# LowLevelv3.net
KiCad netlist of a schematic drawn in EAGLE
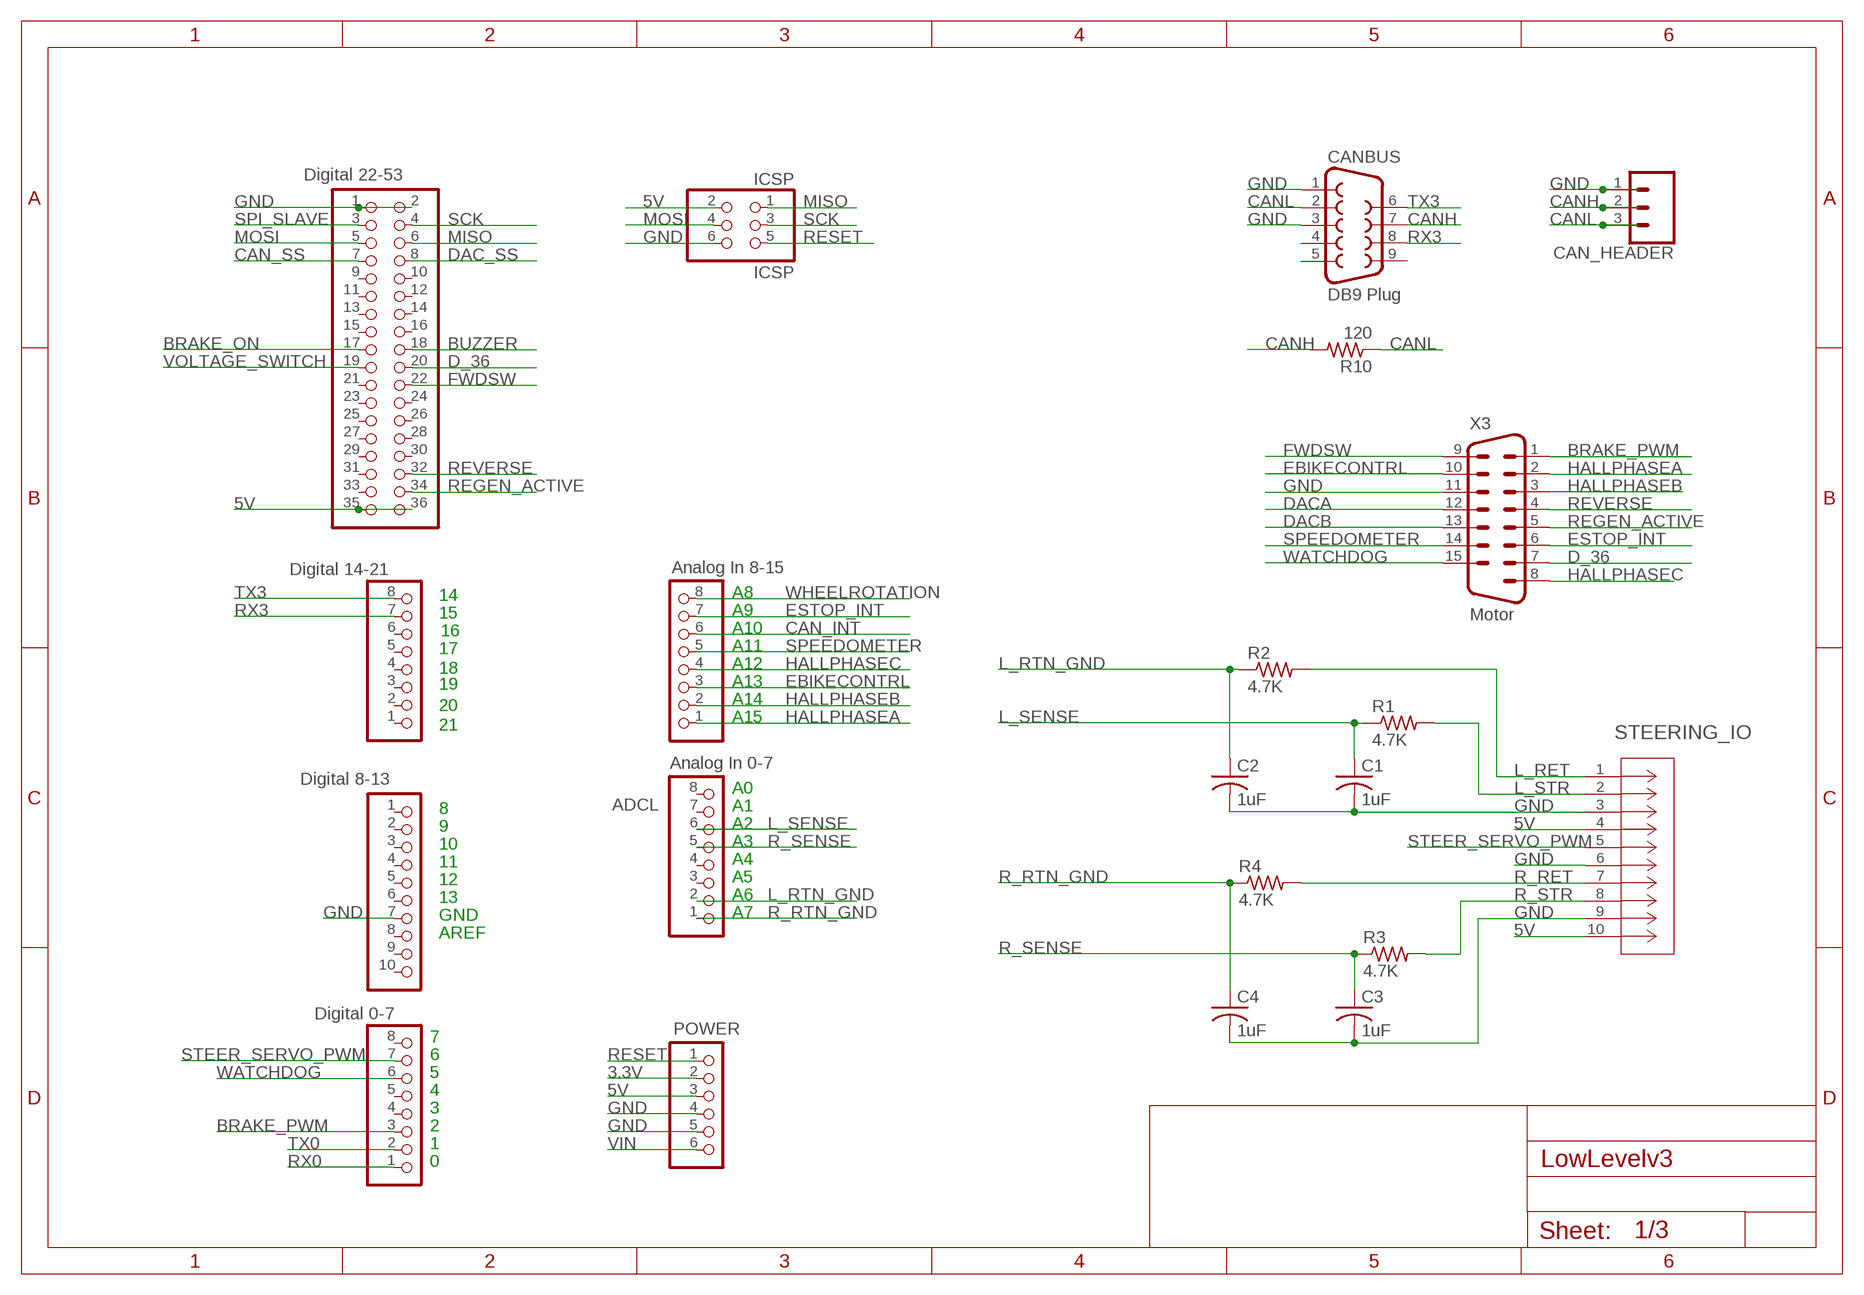
[diagram p0: schematic, sheet 1]
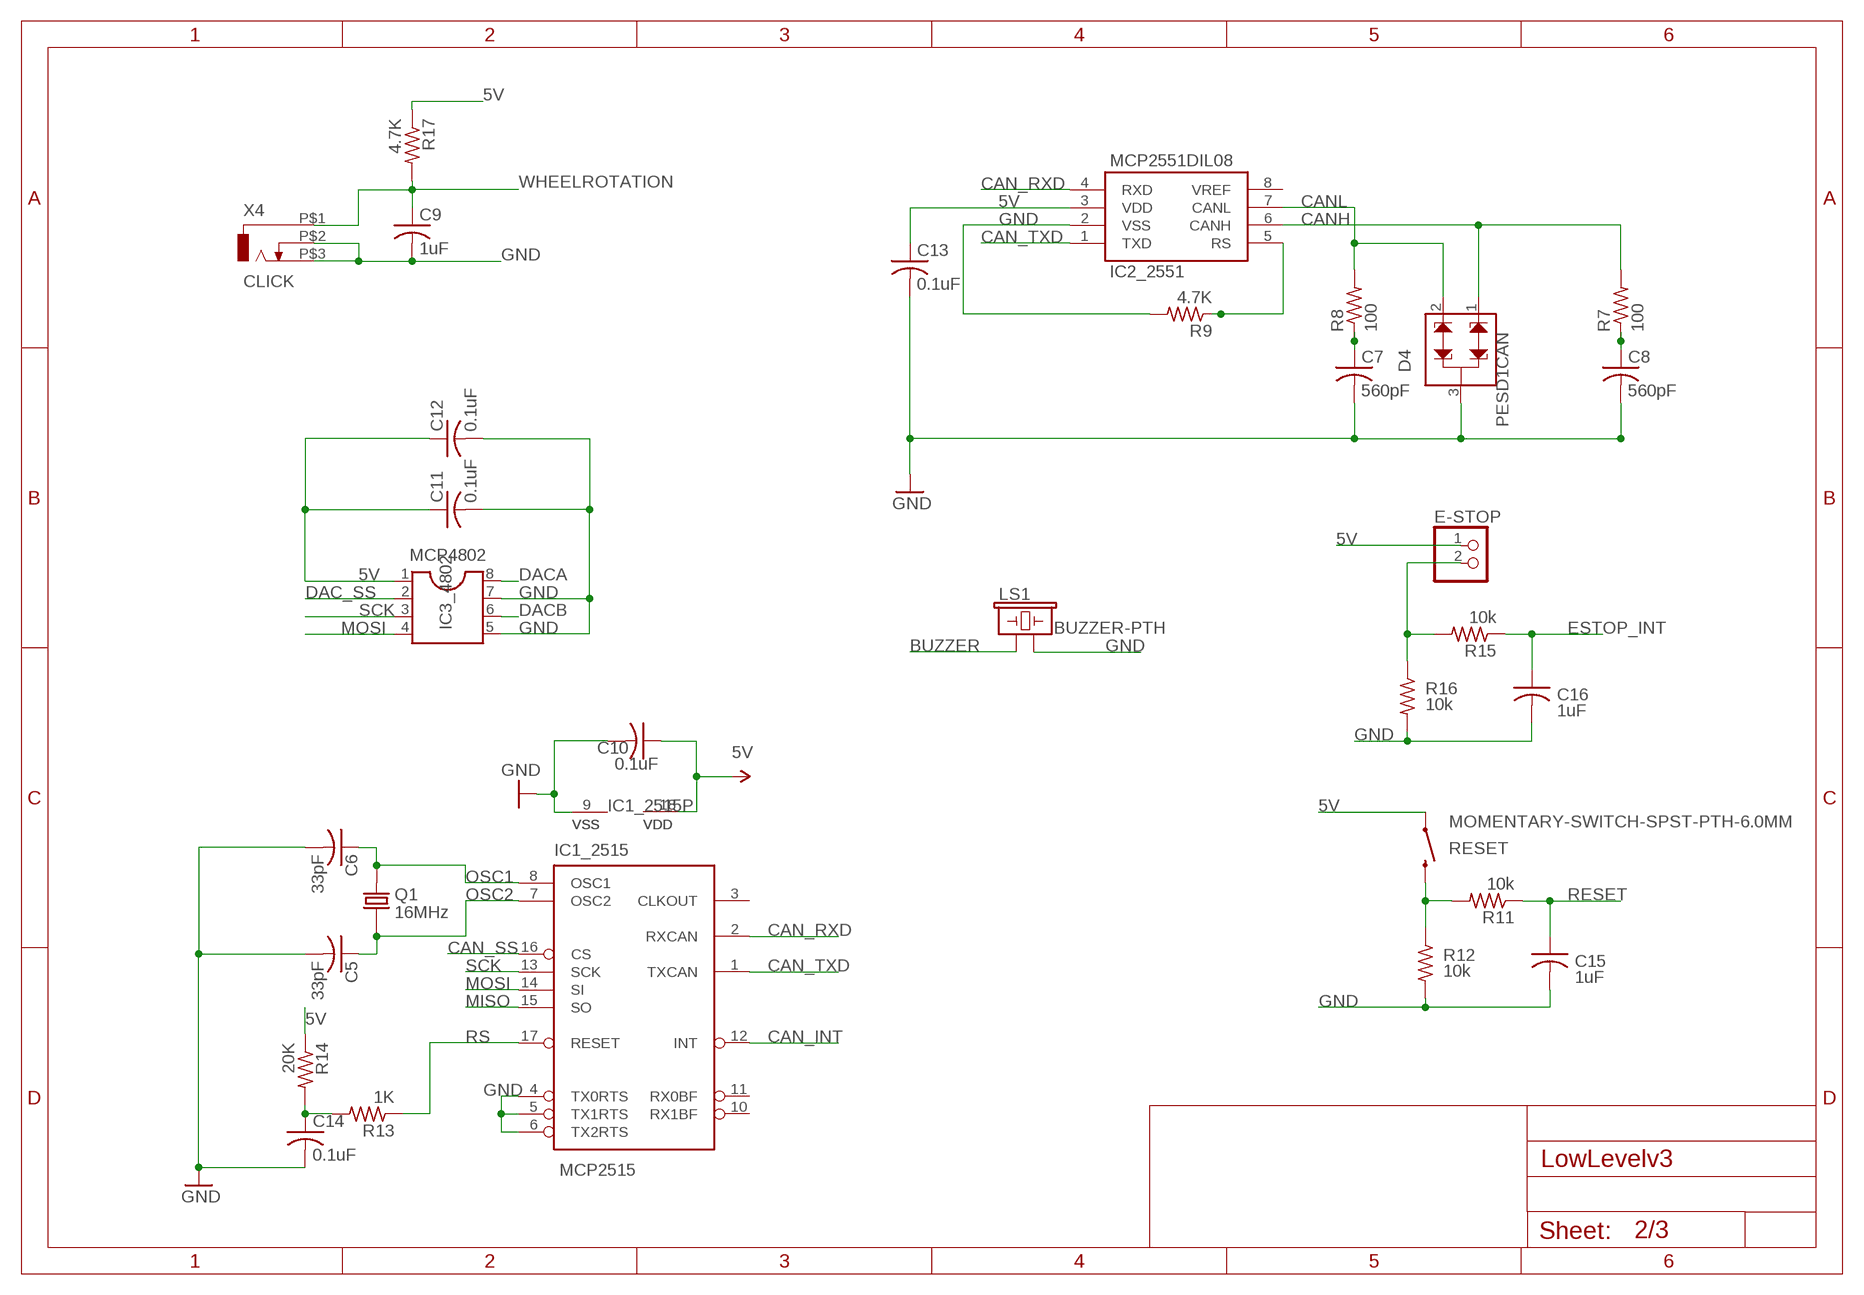
[diagram p1: schematic, sheet 2]
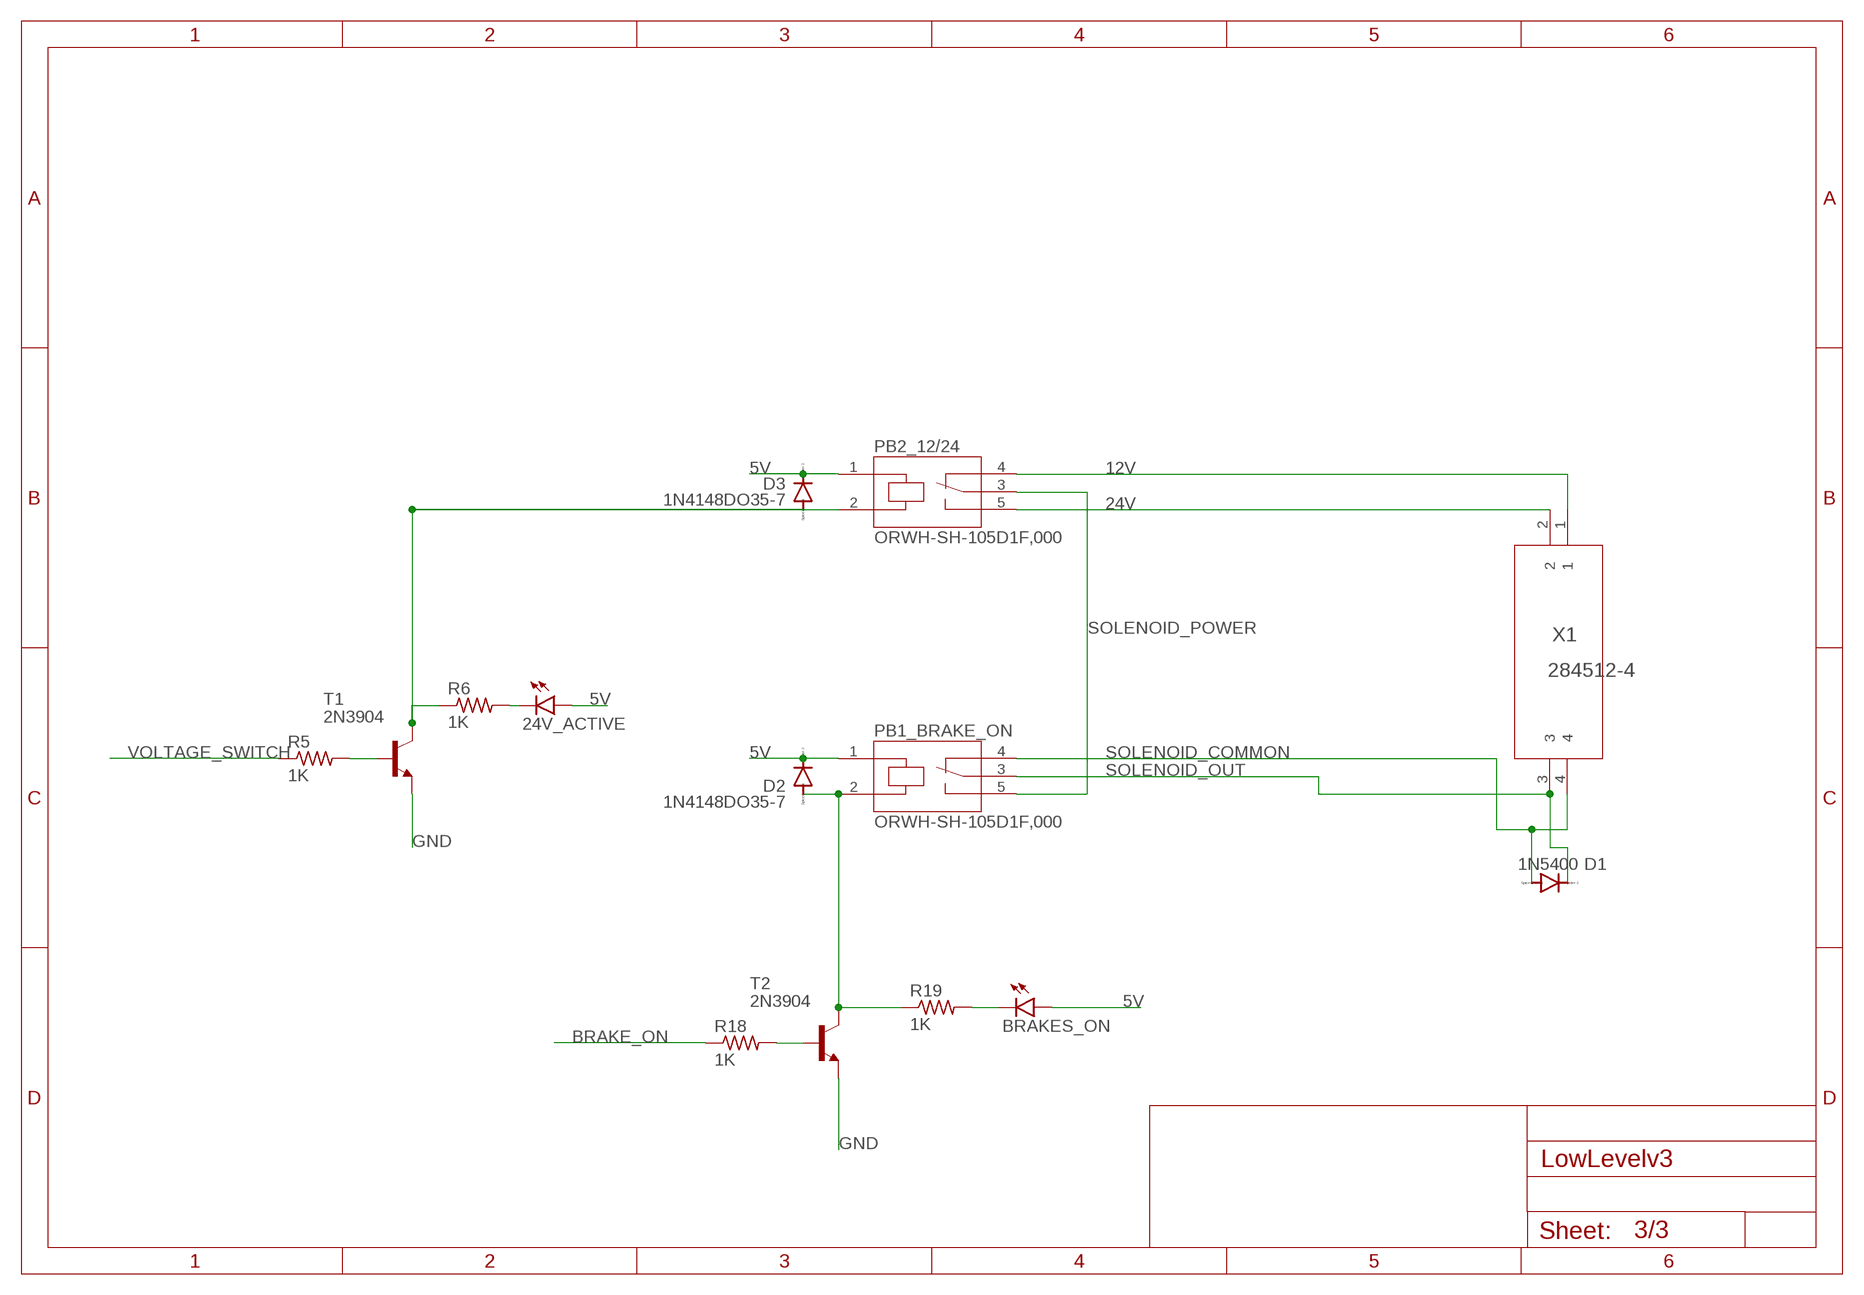
[diagram p2: schematic, sheet 3]

(export (version "E")
  (design (tool "Eeschema 10.0.6"))
  (components
    (comp (ref "ADCH")
      (value "Analog In 8-15")
      (footprint "eagle-import:1X08")
      (libsource (lib "eagle-import") (part "PINHD-1X8"))
    )
    (comp (ref "ADCL")
      (value "Analog In 0-7")
      (footprint "eagle-import:1X08")
      (libsource (lib "eagle-import") (part "PINHD-1X8"))
    )
    (comp (ref "C1")
      (value "1uF")
      (footprint "eagle-import:C1206")
      (libsource (lib "eagle-import") (part "C-USC1206"))
    )
    (comp (ref "C2")
      (value "1uF")
      (footprint "eagle-import:C1206")
      (libsource (lib "eagle-import") (part "C-USC1206"))
    )
    (comp (ref "C3")
      (value "1uF")
      (footprint "eagle-import:C1206")
      (libsource (lib "eagle-import") (part "C-USC1206"))
    )
    (comp (ref "C4")
      (value "1uF")
      (footprint "eagle-import:C1206")
      (libsource (lib "eagle-import") (part "C-USC1206"))
    )
    (comp (ref "CANBUS")
      (value "DB9 Plug")
      (footprint "eagle-import:DB9")
      (fields (field (name "SPICEPREFIX") "X"))
      (libsource (lib "eagle-import") (part "DB9FEMALE"))
    )
    (comp (ref "CAN_HEADER")
      (value "CONN_03-SCREW-5MM")
      (footprint "eagle-import:SCREWTERMINAL-5MM-3")
      (libsource (lib "eagle-import") (part "CONN_03-SCREW-5MM"))
    )
    (comp (ref "DIGITAL_0-7")
      (value "Digital 0-7")
      (footprint "eagle-import:1X08")
      (libsource (lib "eagle-import") (part "PINHD-1X8"))
    )
    (comp (ref "DIGITAL_8-13")
      (value "Digital 8-13")
      (footprint "eagle-import:1X10")
      (libsource (lib "eagle-import") (part "PINHD-1X10"))
    )
    (comp (ref "DIGITAL_14-21")
      (value "Digital 14-21")
      (footprint "eagle-import:1X08")
      (libsource (lib "eagle-import") (part "PINHD-1X8"))
    )
    (comp (ref "ICSP")
      (value "ICSP")
      (footprint "eagle-import:2X03")
      (libsource (lib "eagle-import") (part "PINHD-2X3"))
    )
    (comp (ref "MEGA_EXPANSION")
      (value "Digital 22-53")
      (footprint "eagle-import:PINHEAD_2X18")
      (libsource (lib "eagle-import") (part "PINHEAD_PINHD-2X18"))
    )
    (comp (ref "POWER")
      (value "PINHD-1X6")
      (footprint "eagle-import:1X06")
      (libsource (lib "eagle-import") (part "PINHD-1X6"))
    )
    (comp (ref "R1")
      (value "4.7K")
      (footprint "eagle-import:R1206")
      (libsource (lib "eagle-import") (part "R-US_R1206"))
    )
    (comp (ref "R2")
      (value "4.7K")
      (footprint "eagle-import:R1206")
      (libsource (lib "eagle-import") (part "R-US_R1206"))
    )
    (comp (ref "R3")
      (value "4.7K")
      (footprint "eagle-import:R1206")
      (libsource (lib "eagle-import") (part "R-US_R1206"))
    )
    (comp (ref "R4")
      (value "4.7K")
      (footprint "eagle-import:R1206")
      (libsource (lib "eagle-import") (part "R-US_R1206"))
    )
    (comp (ref "R10")
      (value "120")
      (footprint "eagle-import:R1206")
      (libsource (lib "eagle-import") (part "R-US_R1206"))
    )
    (comp (ref "STEERING_IO")
      (value "5-104069-4")
      (footprint "eagle-import:CONN_5-104069-4_TYCO")
      (fields (field (name "MANUFACTURER_PART_NUMBER") "51040694"))
      (libsource (lib "eagle-import") (part "5-104069-4"))
    )
    (comp (ref "X3")
      (value "Motor")
      (footprint "eagle-import:182-015-MALE")
      (libsource (lib "eagle-import") (part "M15-182"))
    )
    (comp (ref "24V_ACTIVE")
      (value "LED3MM")
      (footprint "eagle-import:LED3MM")
      (libsource (lib "eagle-import") (part "LED3MM"))
    )
    (comp (ref "BRAKES_ON")
      (value "LED3MM")
      (footprint "eagle-import:LED3MM")
      (libsource (lib "eagle-import") (part "LED3MM"))
    )
    (comp (ref "D1")
      (value "1N5400")
      (footprint "eagle-import:DO201-15")
      (libsource (lib "eagle-import") (part "1N5400"))
    )
    (comp (ref "D2")
      (value "1N4148DO35-7")
      (footprint "eagle-import:DO35-7")
      (libsource (lib "eagle-import") (part "1N4148DO35-7"))
    )
    (comp (ref "D3")
      (value "1N4148DO35-7")
      (footprint "eagle-import:DO35-7")
      (libsource (lib "eagle-import") (part "1N4148DO35-7"))
    )
    (comp (ref "PB1_BRAKE_ON")
      (value "ORWH-SH-105D1F,000")
      (footprint "eagle-import:TE_ORWH-SH-105D1F,000")
      (fields (field (name "DIGI-KEY_PART_NUMBER") "PB2032-ND") (field (name "MF") "TE"))
      (libsource (lib "eagle-import") (part "ORWH-SH-105D1F,000"))
    )
    (comp (ref "PB2_12/24")
      (value "ORWH-SH-105D1F,000")
      (footprint "eagle-import:TE_ORWH-SH-105D1F,000")
      (fields (field (name "DIGI-KEY_PART_NUMBER") "PB2032-ND") (field (name "MF") "TE"))
      (libsource (lib "eagle-import") (part "ORWH-SH-105D1F,000"))
    )
    (comp (ref "R5")
      (value "1K")
      (footprint "eagle-import:R1206")
      (libsource (lib "eagle-import") (part "R-US_R1206"))
    )
    (comp (ref "R6")
      (value "1K")
      (footprint "eagle-import:R1206")
      (libsource (lib "eagle-import") (part "R-US_R1206"))
    )
    (comp (ref "R18")
      (value "1K")
      (footprint "eagle-import:R1206")
      (libsource (lib "eagle-import") (part "R-US_R1206"))
    )
    (comp (ref "R19")
      (value "1K")
      (footprint "eagle-import:R1206")
      (libsource (lib "eagle-import") (part "R-US_R1206"))
    )
    (comp (ref "T1")
      (value "2N3904")
      (footprint "eagle-import:TO92")
      (libsource (lib "eagle-import") (part "2N3904"))
    )
    (comp (ref "T2")
      (value "2N3904")
      (footprint "eagle-import:TO92")
      (libsource (lib "eagle-import") (part "2N3904"))
    )
    (comp (ref "X1")
      (value "284512-4")
      (footprint "eagle-import:284512-4")
      (fields (field (name "MANUFACTURER_PART_NUMBER") "2845124"))
      (libsource (lib "eagle-import") (part "284512-4"))
    )
    (comp (ref "C5")
      (value "33pF")
      (footprint "eagle-import:C1206")
      (libsource (lib "eagle-import") (part "C-USC1206"))
    )
    (comp (ref "C6")
      (value "33pF")
      (footprint "eagle-import:C1206")
      (libsource (lib "eagle-import") (part "C-USC1206"))
    )
    (comp (ref "C7")
      (value "560pF")
      (footprint "eagle-import:C1206")
      (libsource (lib "eagle-import") (part "C-USC1206"))
    )
    (comp (ref "C8")
      (value "560pF")
      (footprint "eagle-import:C1206")
      (libsource (lib "eagle-import") (part "C-USC1206"))
    )
    (comp (ref "C9")
      (value "1uF")
      (footprint "eagle-import:C1206")
      (libsource (lib "eagle-import") (part "C-USC1206"))
    )
    (comp (ref "C10")
      (value "0.1uF")
      (footprint "eagle-import:C1206")
      (libsource (lib "eagle-import") (part "C-USC1206"))
    )
    (comp (ref "C11")
      (value "0.1uF")
      (footprint "eagle-import:C1206")
      (libsource (lib "eagle-import") (part "C-USC1206"))
    )
    (comp (ref "C12")
      (value "0.1uF")
      (footprint "eagle-import:C1206")
      (libsource (lib "eagle-import") (part "C-USC1206"))
    )
    (comp (ref "C13")
      (value "0.1uF")
      (footprint "eagle-import:C1206")
      (libsource (lib "eagle-import") (part "C-USC1206"))
    )
    (comp (ref "C14")
      (value "0.1uF")
      (footprint "eagle-import:C1206")
      (libsource (lib "eagle-import") (part "C-USC1206"))
    )
    (comp (ref "C15")
      (value "1uF")
      (footprint "eagle-import:C1206")
      (libsource (lib "eagle-import") (part "C-USC1206"))
    )
    (comp (ref "C16")
      (value "1uF")
      (footprint "eagle-import:C1206")
      (libsource (lib "eagle-import") (part "C-USC1206"))
    )
    (comp (ref "D4")
      (value "PESD1CAN")
      (footprint "eagle-import:SPARKFUN-DISCRETESEMI_SOT23-3")
      (fields (field (name "SPICEPREFIX") "J"))
      (libsource (lib "eagle-import") (part "PESD1CAN"))
    )
    (comp (ref "E-STOP")
      (value "PINHD-1X2")
      (footprint "eagle-import:1X02")
      (libsource (lib "eagle-import") (part "PINHD-1X2"))
    )
    (comp (ref "IC1_2515")
      (value "MCP2515")
      (footprint "eagle-import:DIP18")
      (fields (field (name "SPICEPREFIX") "X"))
      (libsource (lib "eagle-import") (part "MCP2515(MCP2510)P"))
    )
    (comp (ref "IC2_2551")
      (value "MCP2551DIL08")
      (footprint "eagle-import:IC-PACKAGE_DIL08")
      (fields (field (name "SPICEPREFIX") "X"))
      (libsource (lib "eagle-import") (part "MCP2551DIL08"))
    )
    (comp (ref "IC3_4802")
      (value "MCP4802")
      (footprint "eagle-import:DIL08")
      (libsource (lib "eagle-import") (part "DIL8"))
    )
    (comp (ref "LS1")
      (value "BUZZER-PTH")
      (footprint "eagle-import:BUZZER-12MM")
      (libsource (lib "eagle-import") (part "BUZZER-PTH"))
    )
    (comp (ref "Q1")
      (value "16MHz")
      (footprint "eagle-import:XTAL_ECS-160-20-46X")
      (fields
        (field (name "DIGI-KEY_PART_NUMBER") "XC1759-ND")
        (field (name "MF") "ECS Inc.")
        (field (name "MP") "ECS-160-20-46X")
        (field (name "SPICEPREFIX") "B")
      )
      (libsource (lib "eagle-import") (part "ECS-160-20-46X"))
    )
    (comp (ref "R7")
      (value "100")
      (footprint "eagle-import:R1206")
      (libsource (lib "eagle-import") (part "R-US_R1206"))
    )
    (comp (ref "R8")
      (value "100")
      (footprint "eagle-import:R1206")
      (libsource (lib "eagle-import") (part "R-US_R1206"))
    )
    (comp (ref "R9")
      (value "4.7K")
      (footprint "eagle-import:R1206")
      (libsource (lib "eagle-import") (part "R-US_R1206"))
    )
    (comp (ref "R11")
      (value "10k")
      (footprint "eagle-import:R1206")
      (libsource (lib "eagle-import") (part "R-US_R1206"))
    )
    (comp (ref "R12")
      (value "10k")
      (footprint "eagle-import:R1206")
      (libsource (lib "eagle-import") (part "R-US_R1206"))
    )
    (comp (ref "R13")
      (value "1K")
      (footprint "eagle-import:R1206")
      (libsource (lib "eagle-import") (part "R-US_R1206"))
    )
    (comp (ref "R14")
      (value "20K")
      (footprint "eagle-import:R1206")
      (libsource (lib "eagle-import") (part "R-US_R1206"))
    )
    (comp (ref "R15")
      (value "10k")
      (footprint "eagle-import:R1206")
      (libsource (lib "eagle-import") (part "R-US_R1206"))
    )
    (comp (ref "R16")
      (value "10k")
      (footprint "eagle-import:R1206")
      (libsource (lib "eagle-import") (part "R-US_R1206"))
    )
    (comp (ref "R17")
      (value "4.7K")
      (footprint "eagle-import:R1206")
      (libsource (lib "eagle-import") (part "R-US_R1206"))
    )
    (comp (ref "RESET")
      (value "MOMENTARY-SWITCH-SPST-PTH-6.0MM")
      (footprint "eagle-import:TACTILE_SWITCH_PTH_6.0MM")
      (libsource (lib "eagle-import") (part "MOMENTARY-SWITCH-SPST-PTH-6.0MM"))
    )
    (comp (ref "X4")
      (value "CLICK")
      (footprint "eagle-import:ODO_JACK")
      (libsource (lib "eagle-import") (part "ODO_JACK"))
    )
  )
  (nets
    (net (code "1") (name "3.3V") (class "Default")
      (node (ref "POWER") (pin "2") (pinfunction "2_2") (pintype "passive"))
    )
    (net (code "2") (name "5V") (class "Default")
      (node (ref "24V_ACTIVE") (pin "A") (pinfunction "A_A") (pintype "passive"))
      (node (ref "BRAKES_ON") (pin "A") (pinfunction "A_A") (pintype "passive"))
      (node (ref "C10") (pin "1") (pinfunction "1_1") (pintype "passive"))
      (node (ref "C11") (pin "1") (pinfunction "1_1") (pintype "passive"))
      (node (ref "C12") (pin "1") (pinfunction "1_1") (pintype "passive"))
      (node (ref "C13") (pin "1") (pinfunction "1_1") (pintype "passive"))
      (node (ref "D2") (pin "C") (pinfunction "C_C") (pintype "passive"))
      (node (ref "D3") (pin "C") (pinfunction "C_C") (pintype "passive"))
      (node (ref "E-STOP") (pin "1") (pinfunction "1_1") (pintype "passive"))
      (node (ref "IC1_2515") (pin "18") (pinfunction "VDD_18") (pintype "power_in"))
      (node (ref "IC2_2551") (pin "3") (pinfunction "VDD_3") (pintype "bidirectional"))
      (node (ref "IC3_4802") (pin "1") (pinfunction "1_1") (pintype "passive"))
      (node (ref "ICSP") (pin "2") (pinfunction "2_2") (pintype "passive"))
      (node (ref "MEGA_EXPANSION") (pin "35") (pinfunction "35_35") (pintype "passive"))
      (node (ref "MEGA_EXPANSION") (pin "36") (pinfunction "36_36") (pintype "passive"))
      (node (ref "PB1_BRAKE_ON") (pin "1") (pinfunction "C1_1") (pintype "passive"))
      (node (ref "PB2_12/24") (pin "1") (pinfunction "C1_1") (pintype "passive"))
      (node (ref "POWER") (pin "3") (pinfunction "3_3") (pintype "passive"))
      (node (ref "R14") (pin "1") (pinfunction "1_1") (pintype "passive"))
      (node (ref "R17") (pin "1") (pinfunction "1_1") (pintype "passive"))
      (node (ref "RESET") (pin "1") (pinfunction "1_1") (pintype "passive"))
      (node (ref "STEERING_IO") (pin "10") (pinfunction "10_10") (pintype "passive"))
      (node (ref "STEERING_IO") (pin "4") (pinfunction "4_4") (pintype "passive"))
    )
    (net (code "3") (name "12V") (class "Default")
      (node (ref "PB2_12/24") (pin "4") (pinfunction "NC_4") (pintype "passive"))
      (node (ref "X1") (pin "1") (pinfunction "1_1") (pintype "passive"))
    )
    (net (code "4") (name "24V") (class "Default")
      (node (ref "PB2_12/24") (pin "5") (pinfunction "NO_5") (pintype "passive"))
      (node (ref "X1") (pin "2") (pinfunction "2_2") (pintype "passive"))
    )
    (net (code "5") (name "BRAKE_ON") (class "Default")
      (node (ref "MEGA_EXPANSION") (pin "17") (pinfunction "17_17") (pintype "passive"))
      (node (ref "R18") (pin "1") (pinfunction "1_1") (pintype "passive"))
    )
    (net (code "6") (name "BRAKE_PWM") (class "Default")
      (node (ref "DIGITAL_0-7") (pin "3") (pinfunction "3_3") (pintype "passive"))
      (node (ref "X3") (pin "1") (pinfunction "1_1") (pintype "passive"))
    )
    (net (code "7") (name "BUZZER") (class "Default")
      (node (ref "LS1") (pin "+") (pinfunction "1_+") (pintype "passive"))
      (node (ref "MEGA_EXPANSION") (pin "18") (pinfunction "18_18") (pintype "passive"))
    )
    (net (code "8") (name "CANH") (class "Default")
      (node (ref "CANBUS") (pin "7") (pinfunction "7_7") (pintype "passive"))
      (node (ref "CAN_HEADER") (pin "2") (pinfunction "2_2") (pintype "passive"))
      (node (ref "D4") (pin "1") (pinfunction "1_1") (pintype "bidirectional"))
      (node (ref "IC2_2551") (pin "6") (pinfunction "CANH_6") (pintype "bidirectional"))
      (node (ref "R10") (pin "2") (pinfunction "2_2") (pintype "passive"))
      (node (ref "R7") (pin "2") (pinfunction "2_2") (pintype "passive"))
    )
    (net (code "9") (name "CANL") (class "Default")
      (node (ref "CANBUS") (pin "2") (pinfunction "2_2") (pintype "passive"))
      (node (ref "CAN_HEADER") (pin "3") (pinfunction "3_3") (pintype "passive"))
      (node (ref "D4") (pin "2") (pinfunction "2_2") (pintype "bidirectional"))
      (node (ref "IC2_2551") (pin "7") (pinfunction "CANL_7") (pintype "bidirectional"))
      (node (ref "R10") (pin "1") (pinfunction "1_1") (pintype "passive"))
      (node (ref "R8") (pin "2") (pinfunction "2_2") (pintype "passive"))
    )
    (net (code "10") (name "CAN_INT") (class "Default")
      (node (ref "ADCH") (pin "6") (pinfunction "6_6") (pintype "passive"))
      (node (ref "IC1_2515") (pin "12") (pinfunction "INT_12") (pintype "output"))
    )
    (net (code "11") (name "CAN_RXD") (class "Default")
      (node (ref "IC1_2515") (pin "2") (pinfunction "RXCAN_2") (pintype "input"))
      (node (ref "IC2_2551") (pin "4") (pinfunction "RXD_4") (pintype "bidirectional"))
    )
    (net (code "12") (name "CAN_SS") (class "Default")
      (node (ref "IC1_2515") (pin "16") (pinfunction "CS_16") (pintype "input"))
      (node (ref "MEGA_EXPANSION") (pin "7") (pinfunction "7_7") (pintype "passive"))
    )
    (net (code "13") (name "CAN_TXD") (class "Default")
      (node (ref "IC1_2515") (pin "1") (pinfunction "TXCAN_1") (pintype "output"))
      (node (ref "IC2_2551") (pin "1") (pinfunction "TXD_1") (pintype "bidirectional"))
    )
    (net (code "14") (name "DACA") (class "Default")
      (node (ref "IC3_4802") (pin "8") (pinfunction "8_8") (pintype "passive"))
      (node (ref "X3") (pin "12") (pinfunction "12_12") (pintype "passive"))
    )
    (net (code "15") (name "DACB") (class "Default")
      (node (ref "IC3_4802") (pin "6") (pinfunction "6_6") (pintype "passive"))
      (node (ref "X3") (pin "13") (pinfunction "13_13") (pintype "passive"))
    )
    (net (code "16") (name "DAC_SS") (class "Default")
      (node (ref "IC3_4802") (pin "2") (pinfunction "2_2") (pintype "passive"))
      (node (ref "MEGA_EXPANSION") (pin "8") (pinfunction "8_8") (pintype "passive"))
    )
    (net (code "17") (name "D_36") (class "Default")
      (node (ref "MEGA_EXPANSION") (pin "20") (pinfunction "20_20") (pintype "passive"))
      (node (ref "X3") (pin "7") (pinfunction "7_7") (pintype "passive"))
    )
    (net (code "18") (name "EBIKECONTRL") (class "Default")
      (node (ref "ADCH") (pin "3") (pinfunction "3_3") (pintype "passive"))
      (node (ref "X3") (pin "10") (pinfunction "10_10") (pintype "passive"))
    )
    (net (code "19") (name "ESTOP_INT") (class "Default")
      (node (ref "ADCH") (pin "7") (pinfunction "7_7") (pintype "passive"))
      (node (ref "C16") (pin "1") (pinfunction "1_1") (pintype "passive"))
      (node (ref "R15") (pin "1") (pinfunction "1_1") (pintype "passive"))
      (node (ref "X3") (pin "6") (pinfunction "6_6") (pintype "passive"))
    )
    (net (code "20") (name "FWDSW") (class "Default")
      (node (ref "MEGA_EXPANSION") (pin "22") (pinfunction "22_22") (pintype "passive"))
      (node (ref "X3") (pin "9") (pinfunction "9_9") (pintype "passive"))
    )
    (net (code "21") (name "GND") (class "Default")
      (node (ref "C1") (pin "2") (pinfunction "2_2") (pintype "passive"))
      (node (ref "C10") (pin "2") (pinfunction "2_2") (pintype "passive"))
      (node (ref "C11") (pin "2") (pinfunction "2_2") (pintype "passive"))
      (node (ref "C12") (pin "2") (pinfunction "2_2") (pintype "passive"))
      (node (ref "C13") (pin "2") (pinfunction "2_2") (pintype "passive"))
      (node (ref "C14") (pin "2") (pinfunction "2_2") (pintype "passive"))
      (node (ref "C15") (pin "2") (pinfunction "2_2") (pintype "passive"))
      (node (ref "C16") (pin "2") (pinfunction "2_2") (pintype "passive"))
      (node (ref "C2") (pin "2") (pinfunction "2_2") (pintype "passive"))
      (node (ref "C3") (pin "2") (pinfunction "2_2") (pintype "passive"))
      (node (ref "C4") (pin "2") (pinfunction "2_2") (pintype "passive"))
      (node (ref "C5") (pin "2") (pinfunction "2_2") (pintype "passive"))
      (node (ref "C6") (pin "2") (pinfunction "2_2") (pintype "passive"))
      (node (ref "C7") (pin "2") (pinfunction "2_2") (pintype "passive"))
      (node (ref "C8") (pin "2") (pinfunction "2_2") (pintype "passive"))
      (node (ref "C9") (pin "2") (pinfunction "2_2") (pintype "passive"))
      (node (ref "CANBUS") (pin "1") (pinfunction "1_1") (pintype "passive"))
      (node (ref "CANBUS") (pin "3") (pinfunction "3_3") (pintype "passive"))
      (node (ref "CAN_HEADER") (pin "1") (pinfunction "1_1") (pintype "passive"))
      (node (ref "D4") (pin "3") (pinfunction "3_3") (pintype "bidirectional"))
      (node (ref "DIGITAL_8-13") (pin "7") (pinfunction "7_7") (pintype "passive"))
      (node (ref "IC1_2515") (pin "4") (pinfunction "TX0RTS_4") (pintype "input"))
      (node (ref "IC1_2515") (pin "5") (pinfunction "TX1RTS_5") (pintype "input"))
      (node (ref "IC1_2515") (pin "6") (pinfunction "TX2RTS_6") (pintype "input"))
      (node (ref "IC1_2515") (pin "9") (pinfunction "VSS_9") (pintype "power_in"))
      (node (ref "IC2_2551") (pin "2") (pinfunction "VSS_2") (pintype "bidirectional"))
      (node (ref "IC3_4802") (pin "5") (pinfunction "5_5") (pintype "passive"))
      (node (ref "IC3_4802") (pin "7") (pinfunction "7_7") (pintype "passive"))
      (node (ref "ICSP") (pin "6") (pinfunction "6_6") (pintype "passive"))
      (node (ref "LS1") (pin "-") (pinfunction "2_-") (pintype "passive"))
      (node (ref "MEGA_EXPANSION") (pin "1") (pinfunction "1_1") (pintype "passive"))
      (node (ref "MEGA_EXPANSION") (pin "2") (pinfunction "2_2") (pintype "passive"))
      (node (ref "POWER") (pin "4") (pinfunction "4_4") (pintype "passive"))
      (node (ref "POWER") (pin "5") (pinfunction "5_5") (pintype "passive"))
      (node (ref "R12") (pin "2") (pinfunction "2_2") (pintype "passive"))
      (node (ref "R16") (pin "2") (pinfunction "2_2") (pintype "passive"))
      (node (ref "R9") (pin "2") (pinfunction "2_2") (pintype "passive"))
      (node (ref "STEERING_IO") (pin "3") (pinfunction "3_3") (pintype "passive"))
      (node (ref "STEERING_IO") (pin "6") (pinfunction "6_6") (pintype "passive"))
      (node (ref "STEERING_IO") (pin "9") (pinfunction "9_9") (pintype "passive"))
      (node (ref "T1") (pin "3") (pinfunction "E_3") (pintype "passive"))
      (node (ref "T2") (pin "3") (pinfunction "E_3") (pintype "passive"))
      (node (ref "X3") (pin "11") (pinfunction "11_11") (pintype "passive"))
      (node (ref "X4") (pin "P$2") (pinfunction "2_P$2") (pintype "passive"))
      (node (ref "X4") (pin "P$3") (pinfunction "3_P$3") (pintype "passive"))
    )
    (net (code "22") (name "HALLPHASEA") (class "Default")
      (node (ref "ADCH") (pin "1") (pinfunction "1_1") (pintype "passive"))
      (node (ref "X3") (pin "2") (pinfunction "2_2") (pintype "passive"))
    )
    (net (code "23") (name "HALLPHASEB") (class "Default")
      (node (ref "ADCH") (pin "2") (pinfunction "2_2") (pintype "passive"))
      (node (ref "X3") (pin "3") (pinfunction "3_3") (pintype "passive"))
    )
    (net (code "24") (name "HALLPHASEC") (class "Default")
      (node (ref "ADCH") (pin "4") (pinfunction "4_4") (pintype "passive"))
      (node (ref "X3") (pin "8") (pinfunction "8_8") (pintype "passive"))
    )
    (net (code "25") (name "L_RET") (class "Default")
      (node (ref "R2") (pin "2") (pinfunction "2_2") (pintype "passive"))
      (node (ref "STEERING_IO") (pin "1") (pinfunction "1_1") (pintype "passive"))
    )
    (net (code "26") (name "L_RTN_GND") (class "Default")
      (node (ref "ADCL") (pin "2") (pinfunction "2_2") (pintype "passive"))
      (node (ref "C2") (pin "1") (pinfunction "1_1") (pintype "passive"))
      (node (ref "R2") (pin "1") (pinfunction "1_1") (pintype "passive"))
    )
    (net (code "27") (name "L_SENSE") (class "Default")
      (node (ref "ADCL") (pin "6") (pinfunction "6_6") (pintype "passive"))
      (node (ref "C1") (pin "1") (pinfunction "1_1") (pintype "passive"))
      (node (ref "R1") (pin "1") (pinfunction "1_1") (pintype "passive"))
    )
    (net (code "28") (name "L_STR") (class "Default")
      (node (ref "R1") (pin "2") (pinfunction "2_2") (pintype "passive"))
      (node (ref "STEERING_IO") (pin "2") (pinfunction "2_2") (pintype "passive"))
    )
    (net (code "29") (name "MISO") (class "Default")
      (node (ref "IC1_2515") (pin "15") (pinfunction "SO_15") (pintype "output"))
      (node (ref "ICSP") (pin "1") (pinfunction "1_1") (pintype "passive"))
      (node (ref "MEGA_EXPANSION") (pin "6") (pinfunction "6_6") (pintype "passive"))
    )
    (net (code "30") (name "MOSI") (class "Default")
      (node (ref "IC1_2515") (pin "14") (pinfunction "SI_14") (pintype "input"))
      (node (ref "IC3_4802") (pin "4") (pinfunction "4_4") (pintype "passive"))
      (node (ref "ICSP") (pin "4") (pinfunction "4_4") (pintype "passive"))
      (node (ref "MEGA_EXPANSION") (pin "5") (pinfunction "5_5") (pintype "passive"))
    )
    (net (code "31") (name "Net-(24V_ACTIVE-C)") (class "Default")
      (node (ref "24V_ACTIVE") (pin "K") (pinfunction "C_K") (pintype "passive"))
      (node (ref "R6") (pin "2") (pinfunction "2_2") (pintype "passive"))
    )
    (net (code "32") (name "Net-(BRAKES_ON-C)") (class "Default")
      (node (ref "BRAKES_ON") (pin "K") (pinfunction "C_K") (pintype "passive"))
      (node (ref "R19") (pin "2") (pinfunction "2_2") (pintype "passive"))
    )
    (net (code "33") (name "Net-(C7-Pad1)") (class "Default")
      (node (ref "C7") (pin "1") (pinfunction "1_1") (pintype "passive"))
      (node (ref "R8") (pin "1") (pinfunction "1_1") (pintype "passive"))
    )
    (net (code "34") (name "Net-(C8-Pad1)") (class "Default")
      (node (ref "C8") (pin "1") (pinfunction "1_1") (pintype "passive"))
      (node (ref "R7") (pin "1") (pinfunction "1_1") (pintype "passive"))
    )
    (net (code "35") (name "Net-(C14-Pad1)") (class "Default")
      (node (ref "C14") (pin "1") (pinfunction "1_1") (pintype "passive"))
      (node (ref "R13") (pin "2") (pinfunction "2_2") (pintype "passive"))
      (node (ref "R14") (pin "2") (pinfunction "2_2") (pintype "passive"))
    )
    (net (code "36") (name "Net-(E-STOP-Pad2)") (class "Default")
      (node (ref "E-STOP") (pin "2") (pinfunction "2_2") (pintype "passive"))
      (node (ref "R15") (pin "2") (pinfunction "2_2") (pintype "passive"))
      (node (ref "R16") (pin "1") (pinfunction "1_1") (pintype "passive"))
    )
    (net (code "37") (name "Net-(IC2_2551-RS)") (class "Default")
      (node (ref "IC2_2551") (pin "5") (pinfunction "RS_5") (pintype "bidirectional"))
      (node (ref "R9") (pin "1") (pinfunction "1_1") (pintype "passive"))
    )
    (net (code "38") (name "Net-(PB1_BRAKE_ON-C2)") (class "Default")
      (node (ref "D2") (pin "A") (pinfunction "A_A") (pintype "passive"))
      (node (ref "PB1_BRAKE_ON") (pin "2") (pinfunction "C2_2") (pintype "passive"))
      (node (ref "R19") (pin "1") (pinfunction "1_1") (pintype "passive"))
      (node (ref "T2") (pin "1") (pinfunction "C_1") (pintype "passive"))
    )
    (net (code "39") (name "Net-(PB2_12/24-C2)") (class "Default")
      (node (ref "D3") (pin "A") (pinfunction "A_A") (pintype "passive"))
      (node (ref "PB2_12/24") (pin "2") (pinfunction "C2_2") (pintype "passive"))
      (node (ref "R6") (pin "1") (pinfunction "1_1") (pintype "passive"))
      (node (ref "T1") (pin "1") (pinfunction "C_1") (pintype "passive"))
    )
    (net (code "40") (name "Net-(RESET-2)") (class "Default")
      (node (ref "R11") (pin "2") (pinfunction "2_2") (pintype "passive"))
      (node (ref "R12") (pin "1") (pinfunction "1_1") (pintype "passive"))
      (node (ref "RESET") (pin "3") (pinfunction "2_3") (pintype "passive"))
    )
    (net (code "41") (name "Net-(T1-B)") (class "Default")
      (node (ref "R5") (pin "2") (pinfunction "2_2") (pintype "passive"))
      (node (ref "T1") (pin "2") (pinfunction "B_2") (pintype "passive"))
    )
    (net (code "42") (name "Net-(T2-B)") (class "Default")
      (node (ref "R18") (pin "2") (pinfunction "2_2") (pintype "passive"))
      (node (ref "T2") (pin "2") (pinfunction "B_2") (pintype "passive"))
    )
    (net (code "43") (name "OSC1") (class "Default")
      (node (ref "C6") (pin "1") (pinfunction "1_1") (pintype "passive"))
      (node (ref "IC1_2515") (pin "8") (pinfunction "OSC1_8") (pintype "input"))
      (node (ref "Q1") (pin "2") (pinfunction "2_2") (pintype "passive"))
    )
    (net (code "44") (name "OSC2") (class "Default")
      (node (ref "C5") (pin "1") (pinfunction "1_1") (pintype "passive"))
      (node (ref "IC1_2515") (pin "7") (pinfunction "OSC2_7") (pintype "output"))
      (node (ref "Q1") (pin "1") (pinfunction "1_1") (pintype "passive"))
    )
    (net (code "45") (name "REGEN_ACTIVE") (class "Default")
      (node (ref "MEGA_EXPANSION") (pin "34") (pinfunction "34_34") (pintype "passive"))
      (node (ref "X3") (pin "5") (pinfunction "5_5") (pintype "passive"))
    )
    (net (code "46") (name "RESET") (class "Default")
      (node (ref "C15") (pin "1") (pinfunction "1_1") (pintype "passive"))
      (node (ref "ICSP") (pin "5") (pinfunction "5_5") (pintype "passive"))
      (node (ref "POWER") (pin "1") (pinfunction "1_1") (pintype "passive"))
      (node (ref "R11") (pin "1") (pinfunction "1_1") (pintype "passive"))
    )
    (net (code "47") (name "REVERSE") (class "Default")
      (node (ref "MEGA_EXPANSION") (pin "32") (pinfunction "32_32") (pintype "passive"))
      (node (ref "X3") (pin "4") (pinfunction "4_4") (pintype "passive"))
    )
    (net (code "48") (name "RS") (class "Default")
      (node (ref "IC1_2515") (pin "17") (pinfunction "RESET_17") (pintype "input"))
      (node (ref "R13") (pin "1") (pinfunction "1_1") (pintype "passive"))
    )
    (net (code "49") (name "RX0") (class "Default")
      (node (ref "DIGITAL_0-7") (pin "1") (pinfunction "1_1") (pintype "passive"))
    )
    (net (code "50") (name "RX3") (class "Default")
      (node (ref "CANBUS") (pin "8") (pinfunction "8_8") (pintype "passive"))
      (node (ref "DIGITAL_14-21") (pin "7") (pinfunction "7_7") (pintype "passive"))
    )
    (net (code "51") (name "R_RET") (class "Default")
      (node (ref "R4") (pin "2") (pinfunction "2_2") (pintype "passive"))
      (node (ref "STEERING_IO") (pin "7") (pinfunction "7_7") (pintype "passive"))
    )
    (net (code "52") (name "R_RTN_GND") (class "Default")
      (node (ref "ADCL") (pin "1") (pinfunction "1_1") (pintype "passive"))
      (node (ref "C4") (pin "1") (pinfunction "1_1") (pintype "passive"))
      (node (ref "R4") (pin "1") (pinfunction "1_1") (pintype "passive"))
    )
    (net (code "53") (name "R_SENSE") (class "Default")
      (node (ref "ADCL") (pin "5") (pinfunction "5_5") (pintype "passive"))
      (node (ref "C3") (pin "1") (pinfunction "1_1") (pintype "passive"))
      (node (ref "R3") (pin "1") (pinfunction "1_1") (pintype "passive"))
    )
    (net (code "54") (name "R_STR") (class "Default")
      (node (ref "R3") (pin "2") (pinfunction "2_2") (pintype "passive"))
      (node (ref "STEERING_IO") (pin "8") (pinfunction "8_8") (pintype "passive"))
    )
    (net (code "55") (name "SCK") (class "Default")
      (node (ref "IC1_2515") (pin "13") (pinfunction "SCK_13") (pintype "input"))
      (node (ref "IC3_4802") (pin "3") (pinfunction "3_3") (pintype "passive"))
      (node (ref "ICSP") (pin "3") (pinfunction "3_3") (pintype "passive"))
      (node (ref "MEGA_EXPANSION") (pin "4") (pinfunction "4_4") (pintype "passive"))
    )
    (net (code "56") (name "SOLENOID_COMMON") (class "Default")
      (node (ref "D1") (pin "A") (pinfunction "A_A") (pintype "passive"))
      (node (ref "PB1_BRAKE_ON") (pin "4") (pinfunction "NC_4") (pintype "passive"))
      (node (ref "X1") (pin "4") (pinfunction "4_4") (pintype "passive"))
    )
    (net (code "57") (name "SOLENOID_OUT") (class "Default")
      (node (ref "D1") (pin "C") (pinfunction "C_C") (pintype "passive"))
      (node (ref "PB1_BRAKE_ON") (pin "3") (pinfunction "C_3") (pintype "passive"))
      (node (ref "X1") (pin "3") (pinfunction "3_3") (pintype "passive"))
    )
    (net (code "58") (name "SOLENOID_POWER") (class "Default")
      (node (ref "PB1_BRAKE_ON") (pin "5") (pinfunction "NO_5") (pintype "passive"))
      (node (ref "PB2_12/24") (pin "3") (pinfunction "C_3") (pintype "passive"))
    )
    (net (code "59") (name "SPEEDOMETER") (class "Default")
      (node (ref "ADCH") (pin "5") (pinfunction "5_5") (pintype "passive"))
      (node (ref "X3") (pin "14") (pinfunction "14_14") (pintype "passive"))
    )
    (net (code "60") (name "SPI_SLAVE") (class "Default")
      (node (ref "MEGA_EXPANSION") (pin "3") (pinfunction "3_3") (pintype "passive"))
    )
    (net (code "61") (name "STEER_SERVO_PWM") (class "Default")
      (node (ref "DIGITAL_0-7") (pin "7") (pinfunction "7_7") (pintype "passive"))
      (node (ref "STEERING_IO") (pin "5") (pinfunction "5_5") (pintype "passive"))
    )
    (net (code "62") (name "TX0") (class "Default")
      (node (ref "DIGITAL_0-7") (pin "2") (pinfunction "2_2") (pintype "passive"))
    )
    (net (code "63") (name "TX3") (class "Default")
      (node (ref "CANBUS") (pin "6") (pinfunction "6_6") (pintype "passive"))
      (node (ref "DIGITAL_14-21") (pin "8") (pinfunction "8_8") (pintype "passive"))
    )
    (net (code "64") (name "VIN") (class "Default")
      (node (ref "POWER") (pin "6") (pinfunction "6_6") (pintype "passive"))
    )
    (net (code "65") (name "VOLTAGE_SWITCH") (class "Default")
      (node (ref "MEGA_EXPANSION") (pin "19") (pinfunction "19_19") (pintype "passive"))
      (node (ref "R5") (pin "1") (pinfunction "1_1") (pintype "passive"))
    )
    (net (code "66") (name "WATCHDOG") (class "Default")
      (node (ref "DIGITAL_0-7") (pin "6") (pinfunction "6_6") (pintype "passive"))
      (node (ref "X3") (pin "15") (pinfunction "15_15") (pintype "passive"))
    )
    (net (code "67") (name "WHEELROTATION") (class "Default")
      (node (ref "ADCH") (pin "8") (pinfunction "8_8") (pintype "passive"))
      (node (ref "C9") (pin "1") (pinfunction "1_1") (pintype "passive"))
      (node (ref "R17") (pin "2") (pinfunction "2_2") (pintype "passive"))
      (node (ref "X4") (pin "P$1") (pinfunction "1_P$1") (pintype "passive"))
    )
    (net (code "68") (name "unconnected-(ADCL-Pad3)") (class "Default")
      (node (ref "ADCL") (pin "3") (pinfunction "3_3") (pintype "passive"))
    )
    (net (code "69") (name "unconnected-(ADCL-Pad4)") (class "Default")
      (node (ref "ADCL") (pin "4") (pinfunction "4_4") (pintype "passive"))
    )
    (net (code "70") (name "unconnected-(ADCL-Pad7)") (class "Default")
      (node (ref "ADCL") (pin "7") (pinfunction "7_7") (pintype "passive"))
    )
    (net (code "71") (name "unconnected-(ADCL-Pad8)") (class "Default")
      (node (ref "ADCL") (pin "8") (pinfunction "8_8") (pintype "passive"))
    )
    (net (code "72") (name "unconnected-(CANBUS-Pad4)") (class "Default")
      (node (ref "CANBUS") (pin "4") (pinfunction "4_4") (pintype "passive"))
    )
    (net (code "73") (name "unconnected-(CANBUS-Pad5)") (class "Default")
      (node (ref "CANBUS") (pin "5") (pinfunction "5_5") (pintype "passive"))
    )
    (net (code "74") (name "unconnected-(CANBUS-Pad9)") (class "Default")
      (node (ref "CANBUS") (pin "9") (pinfunction "9_9") (pintype "passive"))
    )
    (net (code "75") (name "unconnected-(DIGITAL_0-7-Pad4)") (class "Default")
      (node (ref "DIGITAL_0-7") (pin "4") (pinfunction "4_4") (pintype "passive"))
    )
    (net (code "76") (name "unconnected-(DIGITAL_0-7-Pad5)") (class "Default")
      (node (ref "DIGITAL_0-7") (pin "5") (pinfunction "5_5") (pintype "passive"))
    )
    (net (code "77") (name "unconnected-(DIGITAL_0-7-Pad8)") (class "Default")
      (node (ref "DIGITAL_0-7") (pin "8") (pinfunction "8_8") (pintype "passive"))
    )
    (net (code "78") (name "unconnected-(DIGITAL_8-13-Pad1)") (class "Default")
      (node (ref "DIGITAL_8-13") (pin "1") (pinfunction "1_1") (pintype "passive"))
    )
    (net (code "79") (name "unconnected-(DIGITAL_8-13-Pad2)") (class "Default")
      (node (ref "DIGITAL_8-13") (pin "2") (pinfunction "2_2") (pintype "passive"))
    )
    (net (code "80") (name "unconnected-(DIGITAL_8-13-Pad3)") (class "Default")
      (node (ref "DIGITAL_8-13") (pin "3") (pinfunction "3_3") (pintype "passive"))
    )
    (net (code "81") (name "unconnected-(DIGITAL_8-13-Pad4)") (class "Default")
      (node (ref "DIGITAL_8-13") (pin "4") (pinfunction "4_4") (pintype "passive"))
    )
    (net (code "82") (name "unconnected-(DIGITAL_8-13-Pad5)") (class "Default")
      (node (ref "DIGITAL_8-13") (pin "5") (pinfunction "5_5") (pintype "passive"))
    )
    (net (code "83") (name "unconnected-(DIGITAL_8-13-Pad6)") (class "Default")
      (node (ref "DIGITAL_8-13") (pin "6") (pinfunction "6_6") (pintype "passive"))
    )
    (net (code "84") (name "unconnected-(DIGITAL_8-13-Pad8)") (class "Default")
      (node (ref "DIGITAL_8-13") (pin "8") (pinfunction "8_8") (pintype "passive"))
    )
    (net (code "85") (name "unconnected-(DIGITAL_8-13-Pad9)") (class "Default")
      (node (ref "DIGITAL_8-13") (pin "9") (pinfunction "9_9") (pintype "passive"))
    )
    (net (code "86") (name "unconnected-(DIGITAL_8-13-Pad10)") (class "Default")
      (node (ref "DIGITAL_8-13") (pin "10") (pinfunction "10_10") (pintype "passive"))
    )
    (net (code "87") (name "unconnected-(DIGITAL_14-21-Pad1)") (class "Default")
      (node (ref "DIGITAL_14-21") (pin "1") (pinfunction "1_1") (pintype "passive"))
    )
    (net (code "88") (name "unconnected-(DIGITAL_14-21-Pad2)") (class "Default")
      (node (ref "DIGITAL_14-21") (pin "2") (pinfunction "2_2") (pintype "passive"))
    )
    (net (code "89") (name "unconnected-(DIGITAL_14-21-Pad3)") (class "Default")
      (node (ref "DIGITAL_14-21") (pin "3") (pinfunction "3_3") (pintype "passive"))
    )
    (net (code "90") (name "unconnected-(DIGITAL_14-21-Pad4)") (class "Default")
      (node (ref "DIGITAL_14-21") (pin "4") (pinfunction "4_4") (pintype "passive"))
    )
    (net (code "91") (name "unconnected-(DIGITAL_14-21-Pad5)") (class "Default")
      (node (ref "DIGITAL_14-21") (pin "5") (pinfunction "5_5") (pintype "passive"))
    )
    (net (code "92") (name "unconnected-(DIGITAL_14-21-Pad6)") (class "Default")
      (node (ref "DIGITAL_14-21") (pin "6") (pinfunction "6_6") (pintype "passive"))
    )
    (net (code "93") (name "unconnected-(IC1_2515A-CLKOUT-Pad3)") (class "Default")
      (node (ref "IC1_2515") (pin "3") (pinfunction "CLKOUT_3") (pintype "output"))
    )
    (net (code "94") (name "unconnected-(IC1_2515A-RX0BF-Pad11)") (class "Default")
      (node (ref "IC1_2515") (pin "11") (pinfunction "RX0BF_11") (pintype "output"))
    )
    (net (code "95") (name "unconnected-(IC1_2515A-RX1BF-Pad10)") (class "Default")
      (node (ref "IC1_2515") (pin "10") (pinfunction "RX1BF_10") (pintype "output"))
    )
    (net (code "96") (name "unconnected-(IC2_2551-VREF-Pad8)") (class "Default")
      (node (ref "IC2_2551") (pin "8") (pinfunction "VREF_8") (pintype "bidirectional"))
    )
    (net (code "97") (name "unconnected-(MEGA_EXPANSION-Pad9)") (class "Default")
      (node (ref "MEGA_EXPANSION") (pin "9") (pinfunction "9_9") (pintype "passive"))
    )
    (net (code "98") (name "unconnected-(MEGA_EXPANSION-Pad10)") (class "Default")
      (node (ref "MEGA_EXPANSION") (pin "10") (pinfunction "10_10") (pintype "passive"))
    )
    (net (code "99") (name "unconnected-(MEGA_EXPANSION-Pad11)") (class "Default")
      (node (ref "MEGA_EXPANSION") (pin "11") (pinfunction "11_11") (pintype "passive"))
    )
    (net (code "100") (name "unconnected-(MEGA_EXPANSION-Pad12)") (class "Default")
      (node (ref "MEGA_EXPANSION") (pin "12") (pinfunction "12_12") (pintype "passive"))
    )
    (net (code "101") (name "unconnected-(MEGA_EXPANSION-Pad13)") (class "Default")
      (node (ref "MEGA_EXPANSION") (pin "13") (pinfunction "13_13") (pintype "passive"))
    )
    (net (code "102") (name "unconnected-(MEGA_EXPANSION-Pad14)") (class "Default")
      (node (ref "MEGA_EXPANSION") (pin "14") (pinfunction "14_14") (pintype "passive"))
    )
    (net (code "103") (name "unconnected-(MEGA_EXPANSION-Pad15)") (class "Default")
      (node (ref "MEGA_EXPANSION") (pin "15") (pinfunction "15_15") (pintype "passive"))
    )
    (net (code "104") (name "unconnected-(MEGA_EXPANSION-Pad16)") (class "Default")
      (node (ref "MEGA_EXPANSION") (pin "16") (pinfunction "16_16") (pintype "passive"))
    )
    (net (code "105") (name "unconnected-(MEGA_EXPANSION-Pad21)") (class "Default")
      (node (ref "MEGA_EXPANSION") (pin "21") (pinfunction "21_21") (pintype "passive"))
    )
    (net (code "106") (name "unconnected-(MEGA_EXPANSION-Pad23)") (class "Default")
      (node (ref "MEGA_EXPANSION") (pin "23") (pinfunction "23_23") (pintype "passive"))
    )
    (net (code "107") (name "unconnected-(MEGA_EXPANSION-Pad24)") (class "Default")
      (node (ref "MEGA_EXPANSION") (pin "24") (pinfunction "24_24") (pintype "passive"))
    )
    (net (code "108") (name "unconnected-(MEGA_EXPANSION-Pad25)") (class "Default")
      (node (ref "MEGA_EXPANSION") (pin "25") (pinfunction "25_25") (pintype "passive"))
    )
    (net (code "109") (name "unconnected-(MEGA_EXPANSION-Pad26)") (class "Default")
      (node (ref "MEGA_EXPANSION") (pin "26") (pinfunction "26_26") (pintype "passive"))
    )
    (net (code "110") (name "unconnected-(MEGA_EXPANSION-Pad27)") (class "Default")
      (node (ref "MEGA_EXPANSION") (pin "27") (pinfunction "27_27") (pintype "passive"))
    )
    (net (code "111") (name "unconnected-(MEGA_EXPANSION-Pad28)") (class "Default")
      (node (ref "MEGA_EXPANSION") (pin "28") (pinfunction "28_28") (pintype "passive"))
    )
    (net (code "112") (name "unconnected-(MEGA_EXPANSION-Pad29)") (class "Default")
      (node (ref "MEGA_EXPANSION") (pin "29") (pinfunction "29_29") (pintype "passive"))
    )
    (net (code "113") (name "unconnected-(MEGA_EXPANSION-Pad30)") (class "Default")
      (node (ref "MEGA_EXPANSION") (pin "30") (pinfunction "30_30") (pintype "passive"))
    )
    (net (code "114") (name "unconnected-(MEGA_EXPANSION-Pad31)") (class "Default")
      (node (ref "MEGA_EXPANSION") (pin "31") (pinfunction "31_31") (pintype "passive"))
    )
    (net (code "115") (name "unconnected-(MEGA_EXPANSION-Pad33)") (class "Default")
      (node (ref "MEGA_EXPANSION") (pin "33") (pinfunction "33_33") (pintype "passive"))
    )
  )
)
